# Keo_truot_cua_tu_6_sensor_1_schematic.net
KiCad netlist of a schematic drawn in Altium Designer
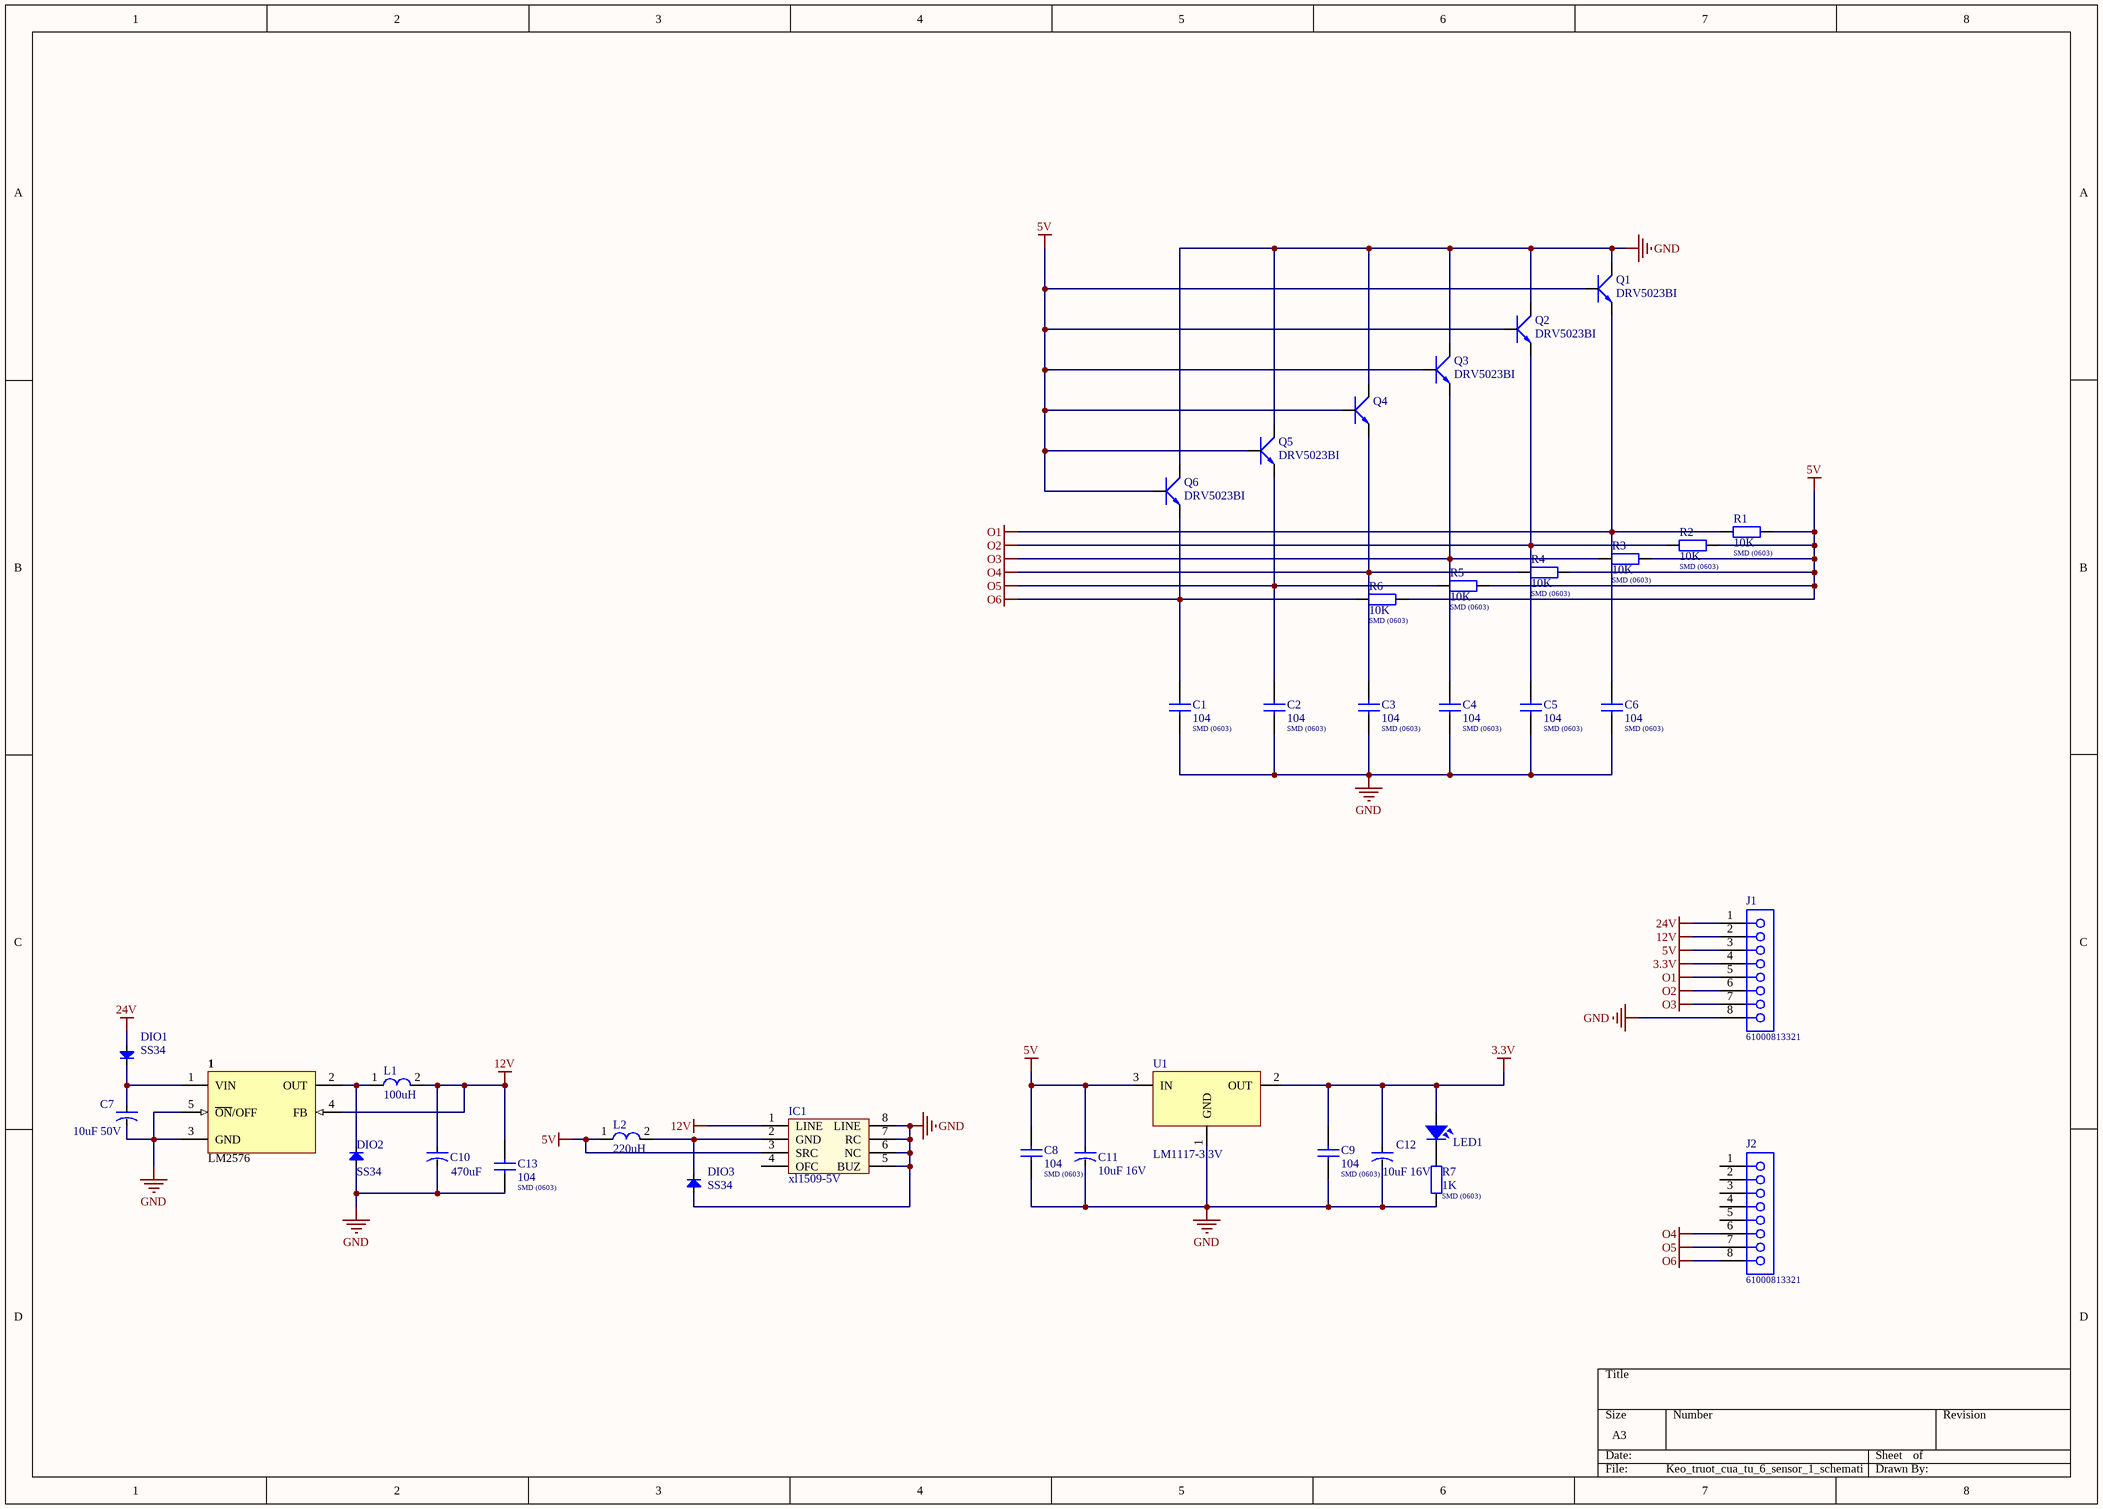
[diagram p0: Keo_truot_cua_tu_6_sensor_1_schematic.SchDoc]

(export (version "E")
  (design (tool "Eeschema 10.0.6"))
  (components
    (comp (ref "1") (value "LM2576") (footprint "TO263") (libsource (lib "LIBRARY") (part "LM2576")))
    (comp (ref "C1")
      (value "104 16V")
      (footprint "CAP_0603")
      (description "Capacitor SMD")
      (fields (field (name "VALOR") "104") (field (name "ENCAPSULAMENTO") "SMD (0603)"))
      (libsource (lib "Altium_Library_Brasil") (part "Capacitor SMD"))
    )
    (comp (ref "C2")
      (value "104 16V")
      (footprint "CAP_0603")
      (description "Capacitor SMD")
      (fields (field (name "VALOR") "104") (field (name "ENCAPSULAMENTO") "SMD (0603)"))
      (libsource (lib "Altium_Library_Brasil") (part "Capacitor SMD"))
    )
    (comp (ref "C3")
      (value "104 16V")
      (footprint "CAP_0603")
      (description "Capacitor SMD")
      (fields (field (name "VALOR") "104") (field (name "ENCAPSULAMENTO") "SMD (0603)"))
      (libsource (lib "Altium_Library_Brasil") (part "Capacitor SMD"))
    )
    (comp (ref "C4")
      (value "104 16V")
      (footprint "CAP_0603")
      (description "Capacitor SMD")
      (fields (field (name "VALOR") "104") (field (name "ENCAPSULAMENTO") "SMD (0603)"))
      (libsource (lib "Altium_Library_Brasil") (part "Capacitor SMD"))
    )
    (comp (ref "C5")
      (value "104 16V")
      (footprint "CAP_0603")
      (description "Capacitor SMD")
      (fields (field (name "VALOR") "104") (field (name "ENCAPSULAMENTO") "SMD (0603)"))
      (libsource (lib "Altium_Library_Brasil") (part "Capacitor SMD"))
    )
    (comp (ref "C6")
      (value "104 16V")
      (footprint "CAP_0603")
      (description "Capacitor SMD")
      (fields (field (name "VALOR") "104") (field (name "ENCAPSULAMENTO") "SMD (0603)"))
      (libsource (lib "Altium_Library_Brasil") (part "Capacitor SMD"))
    )
    (comp (ref "C7")
      (value "10uF 50V")
      (footprint "CAP-ALU-SMD-6.3x7.7x2.2")
      (description "Polarized Capacitor (Axial)")
      (fields (field (name "PUBLISHER") "Altium Limited"))
      (libsource (lib "LIBTanCN") (part "CN-ALU-SMD"))
    )
    (comp (ref "C8")
      (value "104 16V")
      (footprint "CAP_0603")
      (description "Capacitor SMD")
      (fields (field (name "VALOR") "104") (field (name "ENCAPSULAMENTO") "SMD (0603)"))
      (libsource (lib "Altium_Library_Brasil") (part "Capacitor SMD"))
    )
    (comp (ref "C9")
      (value "104 16V")
      (footprint "CAP_0603")
      (description "Capacitor SMD")
      (fields (field (name "VALOR") "104") (field (name "ENCAPSULAMENTO") "SMD (0603)"))
      (libsource (lib "Altium_Library_Brasil") (part "Capacitor SMD"))
    )
    (comp (ref "C10")
      (value "470uF")
      (footprint "CAP-ALU-SMD-6.3x7.7x2.2")
      (description "Polarized Capacitor (Axial)")
      (fields (field (name "PUBLISHER") "Altium Limited"))
      (libsource (lib "LIBTanCN") (part "CN-ALU-SMD"))
    )
    (comp (ref "C11")
      (value "10uF 16V")
      (footprint "CAP-ALU-SMD-4.5x5x1.4")
      (description "Polarized Capacitor (Axial)")
      (fields (field (name "PUBLISHER") "Altium Limited"))
      (libsource (lib "LIBTanCN") (part "CN-ALU-SMD"))
    )
    (comp (ref "C12")
      (value "10uF 16V")
      (footprint "CAP-ALU-SMD-4.5x5x1.4")
      (description "Polarized Capacitor (Axial)")
      (fields (field (name "PUBLISHER") "Altium Limited"))
      (libsource (lib "LIBTanCN") (part "CN-ALU-SMD"))
    )
    (comp (ref "C13")
      (value "104 16V")
      (footprint "CAP_0603")
      (description "Capacitor SMD")
      (fields (field (name "VALOR") "104") (field (name "ENCAPSULAMENTO") "SMD (0603)"))
      (libsource (lib "Altium_Library_Brasil") (part "Capacitor SMD"))
    )
    (comp (ref "DIO1")
      (value "SS34")
      (footprint "DIO-SMD-106")
      (description "Default Diode")
      (fields (field (name "PUBLISHER") "Altium Limited"))
      (libsource (lib "LIBRARY") (part "Diode SMD"))
    )
    (comp (ref "DIO2")
      (value "SS34")
      (footprint "DIO-SMD-106")
      (description "Default Diode")
      (fields (field (name "PUBLISHER") "Altium Limited"))
      (libsource (lib "LIBRARY") (part "Diode SMD"))
    )
    (comp (ref "DIO3")
      (value "SS34")
      (footprint "DIO-SMD-106")
      (description "Default Diode")
      (fields (field (name "PUBLISHER") "Altium Limited"))
      (libsource (lib "LIBRARY") (part "Diode SMD"))
    )
    (comp (ref "IC1")
      (value "xl1509-5V")
      (footprint "SO-8")
      (description "Electronic Two-Tone Ringer")
      (libsource (lib "LIBTanCN") (part "LS1240A"))
    )
    (comp (ref "J1")
      (value "61000813321")
      (footprint "61000813321")
      (description "SMT Vertical Socket Header WR-PHD, Pitch 2.54 mm, Single Row, 8 pins")
      (fields (field (name "PUBLISHER") "Wurth Elektronik"))
      (libsource (lib "Jumpcai_2.54") (part "61000813321"))
    )
    (comp (ref "J2")
      (value "61000813321")
      (footprint "61000813321")
      (description "SMT Vertical Socket Header WR-PHD, Pitch 2.54 mm, Single Row, 8 pins")
      (fields (field (name "PUBLISHER") "Wurth Elektronik"))
      (libsource (lib "Jumpcai_2.54") (part "61000813321"))
    )
    (comp (ref "L1")
      (value "100uH")
      (footprint "L-SMD-M-12x10")
      (fields
        (field (name "PARTNO") "78477010")
        (field (name "MANUFACTURER") "Wurth Elektronik")
        (field (name "CREATED BY") "Baojun Chen")
      )
      (libsource (lib "LIBRARY") (part "L-SMD-1"))
    )
    (comp (ref "L2")
      (value "220uH")
      (footprint "L-SMD-M-7.3x4.5")
      (fields
        (field (name "PARTNO") "78477010")
        (field (name "MANUFACTURER") "Wurth Elektronik")
        (field (name "CREATED BY") "Baojun Chen")
      )
      (libsource (lib "LIBRARY") (part "L-SMD-1"))
    )
    (comp (ref "LED1") (value "LED") (footprint "LED-0805-Red") (libsource (lib "LIBRARY") (part "LED SMD")))
    (comp (ref "Q1")
      (value "DRV5023BI")
      (footprint "SOT23B")
      (description "hall sensor")
      (libsource (lib "electronicvn-library1") (part "C1815"))
    )
    (comp (ref "Q2")
      (value "DRV5023BI")
      (footprint "SOT23B")
      (description "hall sensor")
      (libsource (lib "electronicvn-library1") (part "C1815"))
    )
    (comp (ref "Q3")
      (value "DRV5023BI")
      (footprint "SOT23B")
      (description "hall sensor")
      (libsource (lib "electronicvn-library1") (part "C1815"))
    )
    (comp (ref "Q4")
      (value "DRV5023BI")
      (footprint "SOT23B")
      (description "hall sensor")
      (libsource (lib "electronicvn-library1") (part "C1815"))
    )
    (comp (ref "Q5")
      (value "DRV5023BI")
      (footprint "SOT23B")
      (description "hall sensor")
      (libsource (lib "electronicvn-library1") (part "C1815"))
    )
    (comp (ref "Q6")
      (value "DRV5023BI")
      (footprint "SOT23B")
      (description "hall sensor")
      (libsource (lib "electronicvn-library1") (part "C1815"))
    )
    (comp (ref "R1")
      (value "10K")
      (footprint "RES_0603")
      (description "Resistor SMD")
      (fields (field (name "VALOR") "10K") (field (name "ENCAPSULAMENTO") "SMD (0603)"))
      (libsource (lib "Altium_Library_Brasil") (part "Resistor SMD"))
    )
    (comp (ref "R2")
      (value "10K")
      (footprint "RES_0603")
      (description "Resistor SMD")
      (fields (field (name "VALOR") "10K") (field (name "ENCAPSULAMENTO") "SMD (0603)"))
      (libsource (lib "Altium_Library_Brasil") (part "Resistor SMD"))
    )
    (comp (ref "R3")
      (value "10K")
      (footprint "RES_0603")
      (description "Resistor SMD")
      (fields (field (name "VALOR") "10K") (field (name "ENCAPSULAMENTO") "SMD (0603)"))
      (libsource (lib "Altium_Library_Brasil") (part "Resistor SMD"))
    )
    (comp (ref "R4")
      (value "10K")
      (footprint "RES_0603")
      (description "Resistor SMD")
      (fields (field (name "VALOR") "10K") (field (name "ENCAPSULAMENTO") "SMD (0603)"))
      (libsource (lib "Altium_Library_Brasil") (part "Resistor SMD"))
    )
    (comp (ref "R5")
      (value "10K")
      (footprint "RES_0603")
      (description "Resistor SMD")
      (fields (field (name "VALOR") "10K") (field (name "ENCAPSULAMENTO") "SMD (0603)"))
      (libsource (lib "Altium_Library_Brasil") (part "Resistor SMD"))
    )
    (comp (ref "R6")
      (value "10K")
      (footprint "RES_0603")
      (description "Resistor SMD")
      (fields (field (name "VALOR") "10K") (field (name "ENCAPSULAMENTO") "SMD (0603)"))
      (libsource (lib "Altium_Library_Brasil") (part "Resistor SMD"))
    )
    (comp (ref "R7")
      (value "1K")
      (footprint "RES_0603")
      (description "Resistor SMD")
      (fields (field (name "VALOR") "1K") (field (name "ENCAPSULAMENTO") "SMD (0603)"))
      (libsource (lib "") (part "Resistor SMD_1"))
    )
    (comp (ref "U1")
      (value "LM1117-3.3V")
      (footprint "SOT223")
      (description "800mA Low-Dropout Linear Regulator")
      (fields (field (name "CREATOR") "Nguyen Ba Bien"))
      (libsource (lib "LIBRARY") (part "LM1117"))
    )
  )
  (nets
    (net (code "1") (name "3.3V") (class "Default")
      (node (ref "C12") (pin "1") (pinfunction "1_1") (pintype "passive"))
      (node (ref "C9") (pin "2") (pinfunction "2_2") (pintype "passive"))
      (node (ref "J1") (pin "4") (pinfunction "4_4") (pintype "passive"))
      (node (ref "LED1") (pin "1") (pinfunction "1_1") (pintype "passive"))
      (node (ref "U1") (pin "2") (pinfunction "OUT_2") (pintype "passive"))
    )
    (net (code "2") (name "5V") (class "Default")
      (node (ref "C11") (pin "1") (pinfunction "1_1") (pintype "passive"))
      (node (ref "C8") (pin "2") (pinfunction "2_2") (pintype "passive"))
      (node (ref "IC1") (pin "3") (pinfunction "SRC_3") (pintype "passive"))
      (node (ref "J1") (pin "3") (pinfunction "3_3") (pintype "passive"))
      (node (ref "L2") (pin "1") (pinfunction "1_1") (pintype "passive"))
      (node (ref "Q1") (pin "3") (pinfunction "B_3") (pintype "passive"))
      (node (ref "Q2") (pin "3") (pinfunction "B_3") (pintype "passive"))
      (node (ref "Q3") (pin "3") (pinfunction "B_3") (pintype "passive"))
      (node (ref "Q4") (pin "3") (pinfunction "B_3") (pintype "passive"))
      (node (ref "Q5") (pin "3") (pinfunction "B_3") (pintype "passive"))
      (node (ref "Q6") (pin "3") (pinfunction "B_3") (pintype "passive"))
      (node (ref "R1") (pin "2") (pinfunction "2_2") (pintype "passive"))
      (node (ref "R2") (pin "2") (pinfunction "2_2") (pintype "passive"))
      (node (ref "R3") (pin "2") (pinfunction "2_2") (pintype "passive"))
      (node (ref "R4") (pin "2") (pinfunction "2_2") (pintype "passive"))
      (node (ref "R5") (pin "2") (pinfunction "2_2") (pintype "passive"))
      (node (ref "R6") (pin "2") (pinfunction "2_2") (pintype "passive"))
      (node (ref "U1") (pin "3") (pinfunction "IN_3") (pintype "passive"))
    )
    (net (code "3") (name "12V") (class "Default")
      (node (ref "1") (pin "4") (pinfunction "FB_4") (pintype "input"))
      (node (ref "C10") (pin "1") (pinfunction "1_1") (pintype "passive"))
      (node (ref "C13") (pin "2") (pinfunction "2_2") (pintype "passive"))
      (node (ref "IC1") (pin "1") (pinfunction "LINE_1") (pintype "passive"))
      (node (ref "J1") (pin "2") (pinfunction "2_2") (pintype "passive"))
      (node (ref "L1") (pin "2") (pinfunction "2_2") (pintype "passive"))
    )
    (net (code "4") (name "24V") (class "Default")
      (node (ref "DIO1") (pin "1") (pinfunction "A_1") (pintype "passive"))
      (node (ref "J1") (pin "1") (pinfunction "1_1") (pintype "passive"))
    )
    (net (code "5") (name "GND") (class "Default")
      (node (ref "1") (pin "3") (pinfunction "GND_3") (pintype "power_in"))
      (node (ref "1") (pin "5") (pinfunction "~{ON}/OFF_5") (pintype "input"))
      (node (ref "C1") (pin "1") (pinfunction "1_1") (pintype "passive"))
      (node (ref "C10") (pin "2") (pinfunction "2_2") (pintype "passive"))
      (node (ref "C11") (pin "2") (pinfunction "2_2") (pintype "passive"))
      (node (ref "C12") (pin "2") (pinfunction "2_2") (pintype "passive"))
      (node (ref "C13") (pin "1") (pinfunction "1_1") (pintype "passive"))
      (node (ref "C2") (pin "1") (pinfunction "1_1") (pintype "passive"))
      (node (ref "C3") (pin "1") (pinfunction "1_1") (pintype "passive"))
      (node (ref "C4") (pin "1") (pinfunction "1_1") (pintype "passive"))
      (node (ref "C5") (pin "1") (pinfunction "1_1") (pintype "passive"))
      (node (ref "C6") (pin "1") (pinfunction "1_1") (pintype "passive"))
      (node (ref "C7") (pin "2") (pinfunction "2_2") (pintype "passive"))
      (node (ref "C8") (pin "1") (pinfunction "1_1") (pintype "passive"))
      (node (ref "C9") (pin "1") (pinfunction "1_1") (pintype "passive"))
      (node (ref "DIO2") (pin "1") (pinfunction "A_1") (pintype "passive"))
      (node (ref "DIO3") (pin "1") (pinfunction "A_1") (pintype "passive"))
      (node (ref "IC1") (pin "5") (pinfunction "BUZ_5") (pintype "passive"))
      (node (ref "IC1") (pin "6") (pinfunction "NC_6") (pintype "passive"))
      (node (ref "IC1") (pin "7") (pinfunction "RC_7") (pintype "passive"))
      (node (ref "IC1") (pin "8") (pinfunction "LINE_8") (pintype "passive"))
      (node (ref "J1") (pin "8") (pinfunction "8_8") (pintype "passive"))
      (node (ref "Q1") (pin "2") (pinfunction "C_2") (pintype "passive"))
      (node (ref "Q2") (pin "2") (pinfunction "C_2") (pintype "passive"))
      (node (ref "Q3") (pin "2") (pinfunction "C_2") (pintype "passive"))
      (node (ref "Q4") (pin "2") (pinfunction "C_2") (pintype "passive"))
      (node (ref "Q5") (pin "2") (pinfunction "C_2") (pintype "passive"))
      (node (ref "Q6") (pin "2") (pinfunction "C_2") (pintype "passive"))
      (node (ref "R7") (pin "1") (pinfunction "1_1") (pintype "passive"))
      (node (ref "U1") (pin "1") (pinfunction "GND_1") (pintype "passive"))
    )
    (net (code "6") (name "Net-(1-OUT)") (class "Default")
      (node (ref "1") (pin "2") (pinfunction "OUT_2") (pintype "power_in"))
      (node (ref "DIO2") (pin "2") (pinfunction "K_2") (pintype "passive"))
      (node (ref "L1") (pin "1") (pinfunction "1_1") (pintype "passive"))
    )
    (net (code "7") (name "Net-(1-VIN)") (class "Default")
      (node (ref "1") (pin "1") (pinfunction "VIN_1") (pintype "power_in"))
      (node (ref "C7") (pin "1") (pinfunction "1_1") (pintype "passive"))
      (node (ref "DIO1") (pin "2") (pinfunction "K_2") (pintype "passive"))
    )
    (net (code "8") (name "Net-(DIO3-K)") (class "Default")
      (node (ref "DIO3") (pin "2") (pinfunction "K_2") (pintype "passive"))
      (node (ref "IC1") (pin "2") (pinfunction "GND_2") (pintype "passive"))
      (node (ref "L2") (pin "2") (pinfunction "2_2") (pintype "passive"))
    )
    (net (code "9") (name "Net-(LED1-Pad2)") (class "Default")
      (node (ref "LED1") (pin "2") (pinfunction "2_2") (pintype "passive"))
      (node (ref "R7") (pin "2") (pinfunction "2_2") (pintype "passive"))
    )
    (net (code "10") (name "O1") (class "Default")
      (node (ref "C6") (pin "2") (pinfunction "2_2") (pintype "passive"))
      (node (ref "J1") (pin "5") (pinfunction "5_5") (pintype "passive"))
      (node (ref "Q1") (pin "1") (pinfunction "E_1") (pintype "passive"))
      (node (ref "R1") (pin "1") (pinfunction "1_1") (pintype "passive"))
    )
    (net (code "11") (name "O2") (class "Default")
      (node (ref "C5") (pin "2") (pinfunction "2_2") (pintype "passive"))
      (node (ref "J1") (pin "6") (pinfunction "6_6") (pintype "passive"))
      (node (ref "Q2") (pin "1") (pinfunction "E_1") (pintype "passive"))
      (node (ref "R2") (pin "1") (pinfunction "1_1") (pintype "passive"))
    )
    (net (code "12") (name "O3") (class "Default")
      (node (ref "C4") (pin "2") (pinfunction "2_2") (pintype "passive"))
      (node (ref "J1") (pin "7") (pinfunction "7_7") (pintype "passive"))
      (node (ref "Q3") (pin "1") (pinfunction "E_1") (pintype "passive"))
      (node (ref "R3") (pin "1") (pinfunction "1_1") (pintype "passive"))
    )
    (net (code "13") (name "O4") (class "Default")
      (node (ref "C3") (pin "2") (pinfunction "2_2") (pintype "passive"))
      (node (ref "J2") (pin "6") (pinfunction "6_6") (pintype "passive"))
      (node (ref "Q4") (pin "1") (pinfunction "E_1") (pintype "passive"))
      (node (ref "R4") (pin "1") (pinfunction "1_1") (pintype "passive"))
    )
    (net (code "14") (name "O5") (class "Default")
      (node (ref "C2") (pin "2") (pinfunction "2_2") (pintype "passive"))
      (node (ref "J2") (pin "7") (pinfunction "7_7") (pintype "passive"))
      (node (ref "Q5") (pin "1") (pinfunction "E_1") (pintype "passive"))
      (node (ref "R5") (pin "1") (pinfunction "1_1") (pintype "passive"))
    )
    (net (code "15") (name "O6") (class "Default")
      (node (ref "C1") (pin "2") (pinfunction "2_2") (pintype "passive"))
      (node (ref "J2") (pin "8") (pinfunction "8_8") (pintype "passive"))
      (node (ref "Q6") (pin "1") (pinfunction "E_1") (pintype "passive"))
      (node (ref "R6") (pin "1") (pinfunction "1_1") (pintype "passive"))
    )
    (net (code "16") (name "unconnected-(IC1-OFC-Pad4)") (class "Default")
      (node (ref "IC1") (pin "4") (pinfunction "OFC_4") (pintype "passive"))
    )
    (net (code "17") (name "unconnected-(J2-Pad1)") (class "Default")
      (node (ref "J2") (pin "1") (pinfunction "1_1") (pintype "passive"))
    )
    (net (code "18") (name "unconnected-(J2-Pad2)") (class "Default")
      (node (ref "J2") (pin "2") (pinfunction "2_2") (pintype "passive"))
    )
    (net (code "19") (name "unconnected-(J2-Pad3)") (class "Default")
      (node (ref "J2") (pin "3") (pinfunction "3_3") (pintype "passive"))
    )
    (net (code "20") (name "unconnected-(J2-Pad4)") (class "Default")
      (node (ref "J2") (pin "4") (pinfunction "4_4") (pintype "passive"))
    )
    (net (code "21") (name "unconnected-(J2-Pad5)") (class "Default")
      (node (ref "J2") (pin "5") (pinfunction "5_5") (pintype "passive"))
    )
  )
)
